# v1_1.net
KiCad netlist of a schematic drawn in EAGLE
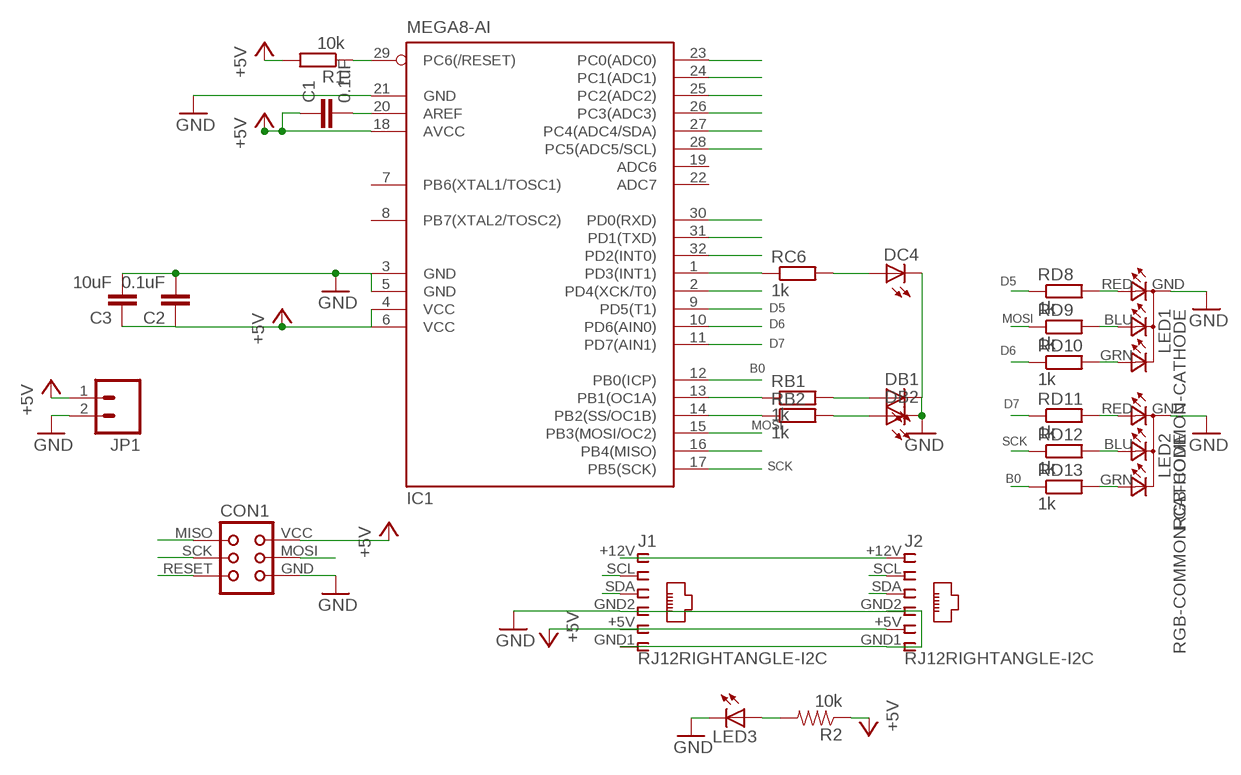
[diagram p0: schematic, sheet 1]

(export (version "E")
  (design (tool "Eeschema 10.0.6"))
  (components
    (comp (ref "C1")
      (value "0.1uF")
      (footprint "eagle-import:C1206")
      (libsource (lib "eagle-import") (part "C-EUC1206"))
    )
    (comp (ref "C2")
      (value "0.1uF")
      (footprint "eagle-import:C1206")
      (libsource (lib "eagle-import") (part "C-EUC1206"))
    )
    (comp (ref "C3")
      (value "10uF")
      (footprint "eagle-import:C1206")
      (libsource (lib "eagle-import") (part "C-EUC1206"))
    )
    (comp (ref "CON1")
      (value "TINYISP")
      (footprint "eagle-import:TINYISP")
      (libsource (lib "eagle-import") (part "TINYISP"))
    )
    (comp (ref "DB1")
      (value "LED3MM")
      (footprint "eagle-import:LED3MM")
      (libsource (lib "eagle-import") (part "led_LED3MM"))
    )
    (comp (ref "DB2")
      (value "LED3MM")
      (footprint "eagle-import:LED3MM")
      (libsource (lib "eagle-import") (part "led_LED3MM"))
    )
    (comp (ref "DC4")
      (value "LED3MM")
      (footprint "eagle-import:LED3MM")
      (libsource (lib "eagle-import") (part "led_LED3MM"))
    )
    (comp (ref "IC1")
      (value "MEGA8-AI")
      (footprint "eagle-import:TQFP32-08")
      (fields (field (name "MPN") "ATMEGA8-16AU"))
      (libsource (lib "eagle-import") (part "MEGA8-AI"))
    )
    (comp (ref "J1")
      (value "RJ12RIGHTANGLE-I2C")
      (footprint "eagle-import:RJ12-RIGHTANGLE-I2C")
      (libsource (lib "eagle-import") (part "RJ12RIGHTANGLE-I2C"))
    )
    (comp (ref "J2")
      (value "RJ12RIGHTANGLE-I2C")
      (footprint "eagle-import:RJ12-RIGHTANGLE-I2C")
      (libsource (lib "eagle-import") (part "RJ12RIGHTANGLE-I2C"))
    )
    (comp (ref "JP1")
      (value "M023.5MM")
      (footprint "eagle-import:SCREWTERMINAL-3.5MM-2")
      (libsource (lib "eagle-import") (part "M023.5MM"))
    )
    (comp (ref "LED1")
      (value "RGB-COMMON-CATHODE")
      (footprint "eagle-import:LED-TRICOLOR-THROUGHHOLE")
      (libsource (lib "eagle-import") (part "RGB-COMMON-CATHODE"))
    )
    (comp (ref "LED2")
      (value "RGB-COMMON-CATHODE")
      (footprint "eagle-import:LED-TRICOLOR-THROUGHHOLE")
      (libsource (lib "eagle-import") (part "RGB-COMMON-CATHODE"))
    )
    (comp (ref "LED3")
      (value "LEDCHIP-LED0603")
      (footprint "eagle-import:CHIP-LED0603")
      (libsource (lib "eagle-import") (part "LEDCHIP-LED0603"))
    )
    (comp (ref "R1")
      (value "10k")
      (footprint "eagle-import:M1206")
      (libsource (lib "eagle-import") (part "R-EU_M1206"))
    )
    (comp (ref "R2")
      (value "10k")
      (footprint "eagle-import:0603-RES")
      (libsource (lib "eagle-import") (part "RESISTOR0603-RES"))
    )
    (comp (ref "RB1")
      (value "1k")
      (footprint "eagle-import:M1206")
      (libsource (lib "eagle-import") (part "R-EU_M1206"))
    )
    (comp (ref "RB2")
      (value "1k")
      (footprint "eagle-import:M1206")
      (libsource (lib "eagle-import") (part "R-EU_M1206"))
    )
    (comp (ref "RC6")
      (value "1k")
      (footprint "eagle-import:M1206")
      (libsource (lib "eagle-import") (part "R-EU_M1206"))
    )
    (comp (ref "RD8")
      (value "1k")
      (footprint "eagle-import:M1206")
      (libsource (lib "eagle-import") (part "R-EU_M1206"))
    )
    (comp (ref "RD9")
      (value "1k")
      (footprint "eagle-import:M1206")
      (libsource (lib "eagle-import") (part "R-EU_M1206"))
    )
    (comp (ref "RD10")
      (value "1k")
      (footprint "eagle-import:M1206")
      (libsource (lib "eagle-import") (part "R-EU_M1206"))
    )
    (comp (ref "RD11")
      (value "1k")
      (footprint "eagle-import:M1206")
      (libsource (lib "eagle-import") (part "R-EU_M1206"))
    )
    (comp (ref "RD12")
      (value "1k")
      (footprint "eagle-import:M1206")
      (libsource (lib "eagle-import") (part "R-EU_M1206"))
    )
    (comp (ref "RD13")
      (value "1k")
      (footprint "eagle-import:M1206")
      (libsource (lib "eagle-import") (part "R-EU_M1206"))
    )
  )
  (nets
    (net (code "1") (name "+5V") (class "Default")
      (node (ref "C1") (pin "1") (pinfunction "1_1") (pintype "passive"))
      (node (ref "C2") (pin "1") (pinfunction "1_1") (pintype "passive"))
      (node (ref "C3") (pin "1") (pinfunction "1_1") (pintype "passive"))
      (node (ref "CON1") (pin "VCC") (pinfunction "VCC_VCC") (pintype "passive"))
      (node (ref "IC1") (pin "18") (pinfunction "AVCC_18") (pintype "power_in"))
      (node (ref "IC1") (pin "4") (pinfunction "VCC_4") (pintype "power_in"))
      (node (ref "IC1") (pin "6") (pinfunction "VCC_6") (pintype "power_in"))
      (node (ref "J1") (pin "+5V") (pinfunction "5_+5V") (pintype "power_in"))
      (node (ref "J2") (pin "+5V") (pinfunction "5_+5V") (pintype "power_in"))
      (node (ref "JP1") (pin "1") (pinfunction "1_1") (pintype "passive"))
      (node (ref "R1") (pin "2") (pinfunction "2_2") (pintype "passive"))
      (node (ref "R2") (pin "1") (pinfunction "1_1") (pintype "passive"))
    )
    (net (code "2") (name "/B0") (class "Default")
      (node (ref "IC1") (pin "12") (pinfunction "PB0(ICP)_12") (pintype "bidirectional"))
      (node (ref "RD13") (pin "1") (pinfunction "1_1") (pintype "passive"))
    )
    (net (code "3") (name "/D5") (class "Default")
      (node (ref "IC1") (pin "9") (pinfunction "PD5(T1)_9") (pintype "bidirectional"))
      (node (ref "RD8") (pin "1") (pinfunction "1_1") (pintype "passive"))
    )
    (net (code "4") (name "/D6") (class "Default")
      (node (ref "IC1") (pin "10") (pinfunction "PD6(AIN0)_10") (pintype "bidirectional"))
      (node (ref "RD10") (pin "1") (pinfunction "1_1") (pintype "passive"))
    )
    (net (code "5") (name "/D7") (class "Default")
      (node (ref "IC1") (pin "11") (pinfunction "PD7(AIN1)_11") (pintype "bidirectional"))
      (node (ref "RD11") (pin "1") (pinfunction "1_1") (pintype "passive"))
    )
    (net (code "6") (name "/MISO") (class "Default")
      (node (ref "CON1") (pin "MISO") (pinfunction "MISO_MISO") (pintype "passive"))
      (node (ref "IC1") (pin "16") (pinfunction "PB4(MISO)_16") (pintype "bidirectional"))
    )
    (net (code "7") (name "/MOSI") (class "Default")
      (node (ref "CON1") (pin "MOSI") (pinfunction "MOSI_MOSI") (pintype "passive"))
      (node (ref "IC1") (pin "15") (pinfunction "PB3(MOSI/OC2)_15") (pintype "bidirectional"))
      (node (ref "RD9") (pin "1") (pinfunction "1_1") (pintype "passive"))
    )
    (net (code "8") (name "/RESET") (class "Default")
      (node (ref "CON1") (pin "RESET") (pinfunction "RESET_RESET") (pintype "passive"))
      (node (ref "IC1") (pin "29") (pinfunction "PC6(/RESET)_29") (pintype "bidirectional"))
      (node (ref "R1") (pin "1") (pinfunction "1_1") (pintype "passive"))
    )
    (net (code "9") (name "/SCK") (class "Default")
      (node (ref "CON1") (pin "SCK") (pinfunction "SCK_SCK") (pintype "passive"))
      (node (ref "IC1") (pin "17") (pinfunction "PB5(SCK)_17") (pintype "bidirectional"))
      (node (ref "RD12") (pin "1") (pinfunction "1_1") (pintype "passive"))
    )
    (net (code "10") (name "/SCL") (class "Default")
      (node (ref "IC1") (pin "28") (pinfunction "PC5(ADC5/SCL)_28") (pintype "bidirectional"))
      (node (ref "J1") (pin "SCL") (pinfunction "2_SCL") (pintype "bidirectional"))
      (node (ref "J2") (pin "SCL") (pinfunction "2_SCL") (pintype "bidirectional"))
    )
    (net (code "11") (name "/SDA") (class "Default")
      (node (ref "IC1") (pin "27") (pinfunction "PC4(ADC4/SDA)_27") (pintype "bidirectional"))
      (node (ref "J1") (pin "SDA") (pinfunction "3_SDA") (pintype "bidirectional"))
      (node (ref "J2") (pin "SDA") (pinfunction "3_SDA") (pintype "bidirectional"))
    )
    (net (code "12") (name "GND") (class "Default")
      (node (ref "C2") (pin "2") (pinfunction "2_2") (pintype "passive"))
      (node (ref "C3") (pin "2") (pinfunction "2_2") (pintype "passive"))
      (node (ref "CON1") (pin "GND") (pinfunction "GND_GND") (pintype "passive"))
      (node (ref "DB1") (pin "K") (pinfunction "C_K") (pintype "passive"))
      (node (ref "DB2") (pin "K") (pinfunction "C_K") (pintype "passive"))
      (node (ref "DC4") (pin "K") (pinfunction "C_K") (pintype "passive"))
      (node (ref "IC1") (pin "21") (pinfunction "GND_21") (pintype "power_in"))
      (node (ref "IC1") (pin "3") (pinfunction "GND_3") (pintype "power_in"))
      (node (ref "IC1") (pin "5") (pinfunction "GND_5") (pintype "power_in"))
      (node (ref "J1") (pin "GND1") (pinfunction "6_GND1") (pintype "power_in"))
      (node (ref "J1") (pin "GND2") (pinfunction "4_GND2") (pintype "power_in"))
      (node (ref "J2") (pin "GND1") (pinfunction "6_GND1") (pintype "power_in"))
      (node (ref "J2") (pin "GND2") (pinfunction "4_GND2") (pintype "power_in"))
      (node (ref "JP1") (pin "2") (pinfunction "2_2") (pintype "passive"))
      (node (ref "LED1") (pin "GND") (pinfunction "A2_GND") (pintype "passive"))
      (node (ref "LED2") (pin "GND") (pinfunction "A2_GND") (pintype "passive"))
      (node (ref "LED3") (pin "C") (pinfunction "C_C") (pintype "passive"))
    )
    (net (code "13") (name "Net-(DB1-PadA)") (class "Default")
      (node (ref "DB1") (pin "A") (pinfunction "A_A") (pintype "passive"))
      (node (ref "RB1") (pin "2") (pinfunction "2_2") (pintype "passive"))
    )
    (net (code "14") (name "Net-(DB2-PadA)") (class "Default")
      (node (ref "DB2") (pin "A") (pinfunction "A_A") (pintype "passive"))
      (node (ref "RB2") (pin "2") (pinfunction "2_2") (pintype "passive"))
    )
    (net (code "15") (name "Net-(DC4-PadA)") (class "Default")
      (node (ref "DC4") (pin "A") (pinfunction "A_A") (pintype "passive"))
      (node (ref "RC6") (pin "2") (pinfunction "2_2") (pintype "passive"))
    )
    (net (code "16") (name "Net-(IC1-AREF)") (class "Default")
      (node (ref "C1") (pin "2") (pinfunction "2_2") (pintype "passive"))
      (node (ref "IC1") (pin "20") (pinfunction "AREF_20") (pintype "passive"))
    )
    (net (code "17") (name "Net-(IC1-PB1(OC1A))") (class "Default")
      (node (ref "IC1") (pin "13") (pinfunction "PB1(OC1A)_13") (pintype "bidirectional"))
      (node (ref "RB1") (pin "1") (pinfunction "1_1") (pintype "passive"))
    )
    (net (code "18") (name "Net-(IC1-PB2(SS{slash}OC1B))") (class "Default")
      (node (ref "IC1") (pin "14") (pinfunction "PB2(SS/OC1B)_14") (pintype "bidirectional"))
      (node (ref "RB2") (pin "1") (pinfunction "1_1") (pintype "passive"))
    )
    (net (code "19") (name "Net-(IC1-PD3(INT1))") (class "Default")
      (node (ref "IC1") (pin "1") (pinfunction "PD3(INT1)_1") (pintype "bidirectional"))
      (node (ref "RC6") (pin "1") (pinfunction "1_1") (pintype "passive"))
    )
    (net (code "20") (name "Net-(J1-1)") (class "Default")
      (node (ref "J1") (pin "+12V") (pinfunction "1_+12V") (pintype "power_in"))
      (node (ref "J2") (pin "+12V") (pinfunction "1_+12V") (pintype "power_in"))
    )
    (net (code "21") (name "Net-(LED1-CBLUE)") (class "Default")
      (node (ref "LED1") (pin "BLU") (pinfunction "CBLUE_BLU") (pintype "passive"))
      (node (ref "RD9") (pin "2") (pinfunction "2_2") (pintype "passive"))
    )
    (net (code "22") (name "Net-(LED1-CGREEN)") (class "Default")
      (node (ref "LED1") (pin "GRN") (pinfunction "CGREEN_GRN") (pintype "passive"))
      (node (ref "RD10") (pin "2") (pinfunction "2_2") (pintype "passive"))
    )
    (net (code "23") (name "Net-(LED1-CRED)") (class "Default")
      (node (ref "LED1") (pin "RED") (pinfunction "CRED_RED") (pintype "passive"))
      (node (ref "RD8") (pin "2") (pinfunction "2_2") (pintype "passive"))
    )
    (net (code "24") (name "Net-(LED2-CBLUE)") (class "Default")
      (node (ref "LED2") (pin "BLU") (pinfunction "CBLUE_BLU") (pintype "passive"))
      (node (ref "RD12") (pin "2") (pinfunction "2_2") (pintype "passive"))
    )
    (net (code "25") (name "Net-(LED2-CGREEN)") (class "Default")
      (node (ref "LED2") (pin "GRN") (pinfunction "CGREEN_GRN") (pintype "passive"))
      (node (ref "RD13") (pin "2") (pinfunction "2_2") (pintype "passive"))
    )
    (net (code "26") (name "Net-(LED2-CRED)") (class "Default")
      (node (ref "LED2") (pin "RED") (pinfunction "CRED_RED") (pintype "passive"))
      (node (ref "RD11") (pin "2") (pinfunction "2_2") (pintype "passive"))
    )
    (net (code "27") (name "Net-(LED3-PadA)") (class "Default")
      (node (ref "LED3") (pin "A") (pinfunction "A_A") (pintype "passive"))
      (node (ref "R2") (pin "2") (pinfunction "2_2") (pintype "passive"))
    )
    (net (code "28") (name "unconnected-(IC1-ADC6-Pad19)") (class "Default")
      (node (ref "IC1") (pin "19") (pinfunction "ADC6_19") (pintype "bidirectional"))
    )
    (net (code "29") (name "unconnected-(IC1-ADC7-Pad22)") (class "Default")
      (node (ref "IC1") (pin "22") (pinfunction "ADC7_22") (pintype "bidirectional"))
    )
    (net (code "30") (name "unconnected-(IC1-PB6(XTAL1{slash}TOSC1)-Pad7)") (class "Default")
      (node (ref "IC1") (pin "7") (pinfunction "PB6(XTAL1/TOSC1)_7") (pintype "bidirectional"))
    )
    (net (code "31") (name "unconnected-(IC1-PB7(XTAL2{slash}TOSC2)-Pad8)") (class "Default")
      (node (ref "IC1") (pin "8") (pinfunction "PB7(XTAL2/TOSC2)_8") (pintype "bidirectional"))
    )
    (net (code "32") (name "unconnected-(IC1-PC0(ADC0)-Pad23)") (class "Default")
      (node (ref "IC1") (pin "23") (pinfunction "PC0(ADC0)_23") (pintype "bidirectional"))
    )
    (net (code "33") (name "unconnected-(IC1-PC1(ADC1)-Pad24)") (class "Default")
      (node (ref "IC1") (pin "24") (pinfunction "PC1(ADC1)_24") (pintype "bidirectional"))
    )
    (net (code "34") (name "unconnected-(IC1-PC2(ADC2)-Pad25)") (class "Default")
      (node (ref "IC1") (pin "25") (pinfunction "PC2(ADC2)_25") (pintype "bidirectional"))
    )
    (net (code "35") (name "unconnected-(IC1-PC3(ADC3)-Pad26)") (class "Default")
      (node (ref "IC1") (pin "26") (pinfunction "PC3(ADC3)_26") (pintype "bidirectional"))
    )
    (net (code "36") (name "unconnected-(IC1-PD0(RXD)-Pad30)") (class "Default")
      (node (ref "IC1") (pin "30") (pinfunction "PD0(RXD)_30") (pintype "bidirectional"))
    )
    (net (code "37") (name "unconnected-(IC1-PD1(TXD)-Pad31)") (class "Default")
      (node (ref "IC1") (pin "31") (pinfunction "PD1(TXD)_31") (pintype "bidirectional"))
    )
    (net (code "38") (name "unconnected-(IC1-PD2(INT0)-Pad32)") (class "Default")
      (node (ref "IC1") (pin "32") (pinfunction "PD2(INT0)_32") (pintype "bidirectional"))
    )
    (net (code "39") (name "unconnected-(IC1-PD4(XCK{slash}T0)-Pad2)") (class "Default")
      (node (ref "IC1") (pin "2") (pinfunction "PD4(XCK/T0)_2") (pintype "bidirectional"))
    )
  )
)
